# Klon.net
KiCad netlist of a schematic drawn in EAGLE
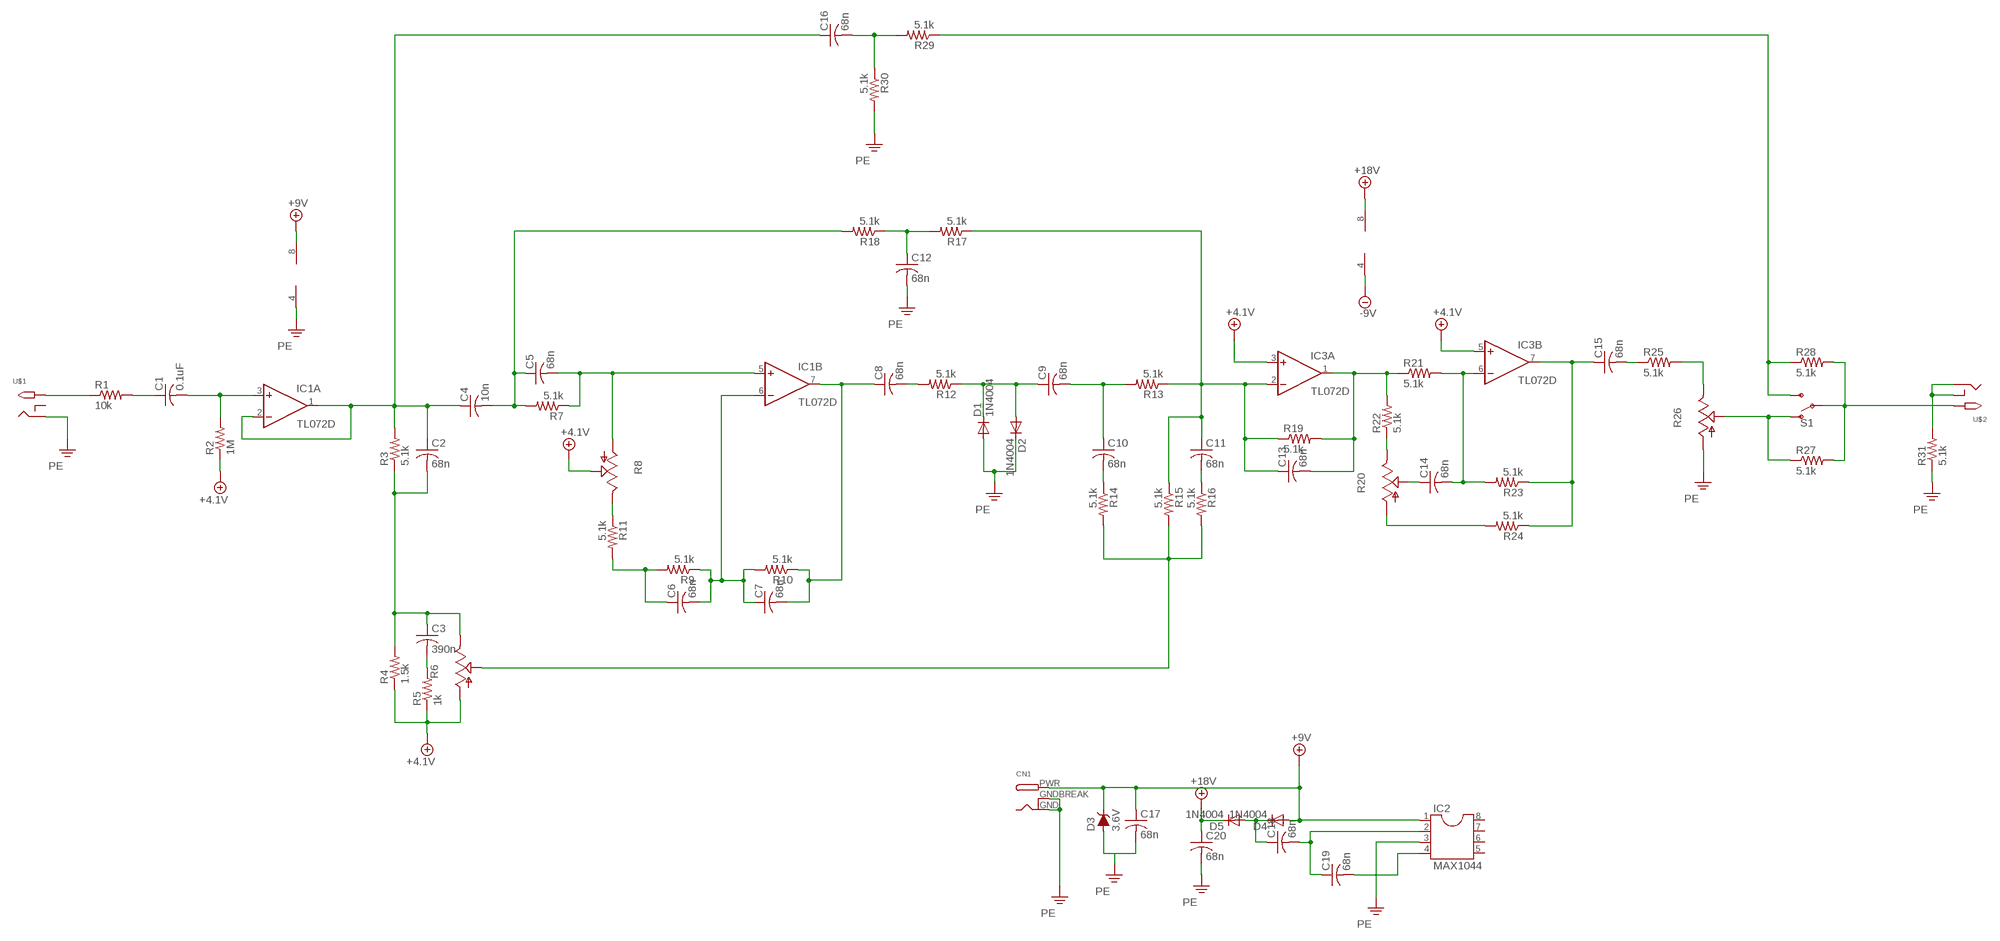
[diagram p0: schematic, sheet 1]

(export (version "E")
  (design (tool "Eeschema 10.0.6"))
  (components
    (comp (ref "C1")
      (value "0.1uF")
      (footprint "eagle-import:C0603")
      (libsource (lib "eagle-import") (part "C-USC0603"))
    )
    (comp (ref "C2")
      (value "68n")
      (footprint "eagle-import:C0603")
      (libsource (lib "eagle-import") (part "C-USC0603"))
    )
    (comp (ref "C3")
      (value "390n")
      (footprint "eagle-import:C0603")
      (libsource (lib "eagle-import") (part "C-USC0603"))
    )
    (comp (ref "C4")
      (value "10n")
      (footprint "eagle-import:C0603")
      (libsource (lib "eagle-import") (part "C-USC0603"))
    )
    (comp (ref "C5")
      (value "68n")
      (footprint "eagle-import:C0603")
      (libsource (lib "eagle-import") (part "C-USC0603"))
    )
    (comp (ref "C6")
      (value "68n")
      (footprint "eagle-import:C0603")
      (libsource (lib "eagle-import") (part "C-USC0603"))
    )
    (comp (ref "C7")
      (value "68n")
      (footprint "eagle-import:C0603")
      (libsource (lib "eagle-import") (part "C-USC0603"))
    )
    (comp (ref "C8")
      (value "68n")
      (footprint "eagle-import:C0603")
      (libsource (lib "eagle-import") (part "C-USC0603"))
    )
    (comp (ref "C9")
      (value "68n")
      (footprint "eagle-import:C0603")
      (libsource (lib "eagle-import") (part "C-USC0603"))
    )
    (comp (ref "C10")
      (value "68n")
      (footprint "eagle-import:C0603")
      (libsource (lib "eagle-import") (part "C-USC0603"))
    )
    (comp (ref "C11")
      (value "68n")
      (footprint "eagle-import:C0603")
      (libsource (lib "eagle-import") (part "C-USC0603"))
    )
    (comp (ref "C12")
      (value "68n")
      (footprint "eagle-import:C0603")
      (libsource (lib "eagle-import") (part "C-USC0603"))
    )
    (comp (ref "C13")
      (value "68n")
      (footprint "eagle-import:C0603")
      (libsource (lib "eagle-import") (part "C-USC0603"))
    )
    (comp (ref "C14")
      (value "68n")
      (footprint "eagle-import:C0603")
      (libsource (lib "eagle-import") (part "C-USC0603"))
    )
    (comp (ref "C15")
      (value "68n")
      (footprint "eagle-import:C0603")
      (libsource (lib "eagle-import") (part "C-USC0603"))
    )
    (comp (ref "C16")
      (value "68n")
      (footprint "eagle-import:C0603")
      (libsource (lib "eagle-import") (part "C-USC0603"))
    )
    (comp (ref "C17")
      (value "68n")
      (footprint "eagle-import:C0603")
      (libsource (lib "eagle-import") (part "C-USC0603"))
    )
    (comp (ref "C18")
      (value "68n")
      (footprint "eagle-import:C0603")
      (libsource (lib "eagle-import") (part "C-USC0603"))
    )
    (comp (ref "C19")
      (value "68n")
      (footprint "eagle-import:C0603")
      (libsource (lib "eagle-import") (part "C-USC0603"))
    )
    (comp (ref "C20")
      (value "68n")
      (footprint "eagle-import:C0603")
      (libsource (lib "eagle-import") (part "C-USC0603"))
    )
    (comp (ref "CN1")
      (value "DCBARRELPTH")
      (footprint "eagle-import:DCJACK_2MM_PTH")
      (libsource (lib "eagle-import") (part "DCBARRELPTH"))
    )
    (comp (ref "D1")
      (value "1N4004")
      (footprint "eagle-import:DO41-10")
      (libsource (lib "eagle-import") (part "1N4004"))
    )
    (comp (ref "D2")
      (value "1N4004")
      (footprint "eagle-import:DO41-10")
      (libsource (lib "eagle-import") (part "1N4004"))
    )
    (comp (ref "D3")
      (value "3.6V")
      (footprint "eagle-import:SOD-323")
      (libsource (lib "eagle-import") (part "DIODE-ZENER-BZT52C3V6S"))
    )
    (comp (ref "D4")
      (value "1N4004")
      (footprint "eagle-import:DO41-10")
      (libsource (lib "eagle-import") (part "1N4004"))
    )
    (comp (ref "D5")
      (value "1N4004")
      (footprint "eagle-import:DO41-10")
      (libsource (lib "eagle-import") (part "1N4004"))
    )
    (comp (ref "IC1")
      (value "TL072D")
      (footprint "eagle-import:SO08")
      (libsource (lib "eagle-import") (part "TL072D"))
    )
    (comp (ref "IC2")
      (value "MAX1044")
      (footprint "eagle-import:DIL08")
      (fields (field (name "MF") "Maxim Integrated"))
      (libsource (lib "eagle-import") (part "MAX1044"))
    )
    (comp (ref "IC3")
      (value "TL072D")
      (footprint "eagle-import:SO08")
      (libsource (lib "eagle-import") (part "TL072D"))
    )
    (comp (ref "R1")
      (value "10k")
      (footprint "eagle-import:R0603")
      (libsource (lib "eagle-import") (part "R-US_R0603"))
    )
    (comp (ref "R2")
      (value "1M")
      (footprint "eagle-import:R0603")
      (libsource (lib "eagle-import") (part "R-US_R0603"))
    )
    (comp (ref "R3")
      (value "5.1k")
      (footprint "eagle-import:R0603")
      (libsource (lib "eagle-import") (part "R-US_R0603"))
    )
    (comp (ref "R4")
      (value "1.5k")
      (footprint "eagle-import:R0603")
      (libsource (lib "eagle-import") (part "R-US_R0603"))
    )
    (comp (ref "R5")
      (value "1k")
      (footprint "eagle-import:R0603")
      (libsource (lib "eagle-import") (part "R-US_R0603"))
    )
    (comp (ref "R6")
      (value "TRIM_US-3223G")
      (footprint "eagle-import:3223G")
      (libsource (lib "eagle-import") (part "TRIM_US-3223G"))
    )
    (comp (ref "R7")
      (value "5.1k")
      (footprint "eagle-import:R0603")
      (libsource (lib "eagle-import") (part "R-US_R0603"))
    )
    (comp (ref "R8")
      (value "TRIM_US-3223G")
      (footprint "eagle-import:3223G")
      (libsource (lib "eagle-import") (part "TRIM_US-3223G"))
    )
    (comp (ref "R9")
      (value "5.1k")
      (footprint "eagle-import:R0603")
      (libsource (lib "eagle-import") (part "R-US_R0603"))
    )
    (comp (ref "R10")
      (value "5.1k")
      (footprint "eagle-import:R0603")
      (libsource (lib "eagle-import") (part "R-US_R0603"))
    )
    (comp (ref "R11")
      (value "5.1k")
      (footprint "eagle-import:R0603")
      (libsource (lib "eagle-import") (part "R-US_R0603"))
    )
    (comp (ref "R12")
      (value "5.1k")
      (footprint "eagle-import:R0603")
      (libsource (lib "eagle-import") (part "R-US_R0603"))
    )
    (comp (ref "R13")
      (value "5.1k")
      (footprint "eagle-import:R0603")
      (libsource (lib "eagle-import") (part "R-US_R0603"))
    )
    (comp (ref "R14")
      (value "5.1k")
      (footprint "eagle-import:R0603")
      (libsource (lib "eagle-import") (part "R-US_R0603"))
    )
    (comp (ref "R15")
      (value "5.1k")
      (footprint "eagle-import:R0603")
      (libsource (lib "eagle-import") (part "R-US_R0603"))
    )
    (comp (ref "R16")
      (value "5.1k")
      (footprint "eagle-import:R0603")
      (libsource (lib "eagle-import") (part "R-US_R0603"))
    )
    (comp (ref "R17")
      (value "5.1k")
      (footprint "eagle-import:R0603")
      (libsource (lib "eagle-import") (part "R-US_R0603"))
    )
    (comp (ref "R18")
      (value "5.1k")
      (footprint "eagle-import:R0603")
      (libsource (lib "eagle-import") (part "R-US_R0603"))
    )
    (comp (ref "R19")
      (value "5.1k")
      (footprint "eagle-import:R0603")
      (libsource (lib "eagle-import") (part "R-US_R0603"))
    )
    (comp (ref "R20")
      (value "TRIM_US-3223G")
      (footprint "eagle-import:3223G")
      (libsource (lib "eagle-import") (part "TRIM_US-3223G"))
    )
    (comp (ref "R21")
      (value "5.1k")
      (footprint "eagle-import:R0603")
      (libsource (lib "eagle-import") (part "R-US_R0603"))
    )
    (comp (ref "R22")
      (value "5.1k")
      (footprint "eagle-import:R0603")
      (libsource (lib "eagle-import") (part "R-US_R0603"))
    )
    (comp (ref "R23")
      (value "5.1k")
      (footprint "eagle-import:R0603")
      (libsource (lib "eagle-import") (part "R-US_R0603"))
    )
    (comp (ref "R24")
      (value "5.1k")
      (footprint "eagle-import:R0603")
      (libsource (lib "eagle-import") (part "R-US_R0603"))
    )
    (comp (ref "R25")
      (value "5.1k")
      (footprint "eagle-import:R0603")
      (libsource (lib "eagle-import") (part "R-US_R0603"))
    )
    (comp (ref "R26")
      (value "TRIM_US-3223G")
      (footprint "eagle-import:3223G")
      (libsource (lib "eagle-import") (part "TRIM_US-3223G"))
    )
    (comp (ref "R27")
      (value "5.1k")
      (footprint "eagle-import:R0603")
      (libsource (lib "eagle-import") (part "R-US_R0603"))
    )
    (comp (ref "R28")
      (value "5.1k")
      (footprint "eagle-import:R0603")
      (libsource (lib "eagle-import") (part "R-US_R0603"))
    )
    (comp (ref "R29")
      (value "5.1k")
      (footprint "eagle-import:R0603")
      (libsource (lib "eagle-import") (part "R-US_R0603"))
    )
    (comp (ref "R30")
      (value "5.1k")
      (footprint "eagle-import:R0603")
      (libsource (lib "eagle-import") (part "R-US_R0603"))
    )
    (comp (ref "R31")
      (value "5.1k")
      (footprint "eagle-import:R0603")
      (libsource (lib "eagle-import") (part "R-US_R0603"))
    )
    (comp (ref "S1")
      (value "SWITCH-SPDT-PTH-11.6X4.0MM")
      (footprint "eagle-import:SWITCH_SPDT_PTH_11.6X4.0MM")
      (libsource (lib "eagle-import") (part "SWITCH-SPDT-PTH-11.6X4.0MM"))
    )
    (comp (ref "U$1")
      (value "2.1MMJACKSMT")
      (footprint "eagle-import:DCJACK_2MM_SMT")
      (libsource (lib "eagle-import") (part "2.1MMJACKSMT"))
    )
    (comp (ref "U$2")
      (value "2.1MMJACKSMT")
      (footprint "eagle-import:DCJACK_2MM_SMT")
      (libsource (lib "eagle-import") (part "2.1MMJACKSMT"))
    )
  )
  (nets
    (net (code "1") (name "+4.1V") (class "Default")
      (node (ref "IC3") (pin "3") (pinfunction "+IN_3") (pintype "input"))
      (node (ref "IC3") (pin "5") (pinfunction "+IN_5") (pintype "input"))
      (node (ref "R2") (pin "1") (pinfunction "1_1") (pintype "passive"))
      (node (ref "R4") (pin "1") (pinfunction "1_1") (pintype "passive"))
      (node (ref "R5") (pin "1") (pinfunction "1_1") (pintype "passive"))
      (node (ref "R6") (pin "1") (pinfunction "A_1") (pintype "passive"))
      (node (ref "R8") (pin "2") (pinfunction "S_2") (pintype "passive"))
    )
    (net (code "2") (name "+9V") (class "Default")
      (node (ref "C17") (pin "1") (pinfunction "1_1") (pintype "passive"))
      (node (ref "CN1") (pin "PWR") (pinfunction "PWR_PWR") (pintype "power_in"))
      (node (ref "D3") (pin "C") (pinfunction "C_C") (pintype "passive"))
      (node (ref "D4") (pin "A") (pinfunction "A_A") (pintype "passive"))
      (node (ref "IC1") (pin "8") (pinfunction "V+_8") (pintype "power_in"))
      (node (ref "IC2") (pin "1") (pinfunction "1_1") (pintype "passive"))
    )
    (net (code "3") (name "+18V") (class "Default")
      (node (ref "C20") (pin "1") (pinfunction "1_1") (pintype "passive"))
      (node (ref "D5") (pin "C") (pinfunction "C_C") (pintype "passive"))
      (node (ref "IC3") (pin "8") (pinfunction "V+_8") (pintype "power_in"))
    )
    (net (code "4") (name "-9V") (class "Default")
      (node (ref "IC3") (pin "4") (pinfunction "V-_4") (pintype "power_in"))
    )
    (net (code "5") (name "Net-(C1-Pad1)") (class "Default")
      (node (ref "C1") (pin "1") (pinfunction "1_1") (pintype "passive"))
      (node (ref "R1") (pin "2") (pinfunction "2_2") (pintype "passive"))
    )
    (net (code "6") (name "Net-(C3-Pad2)") (class "Default")
      (node (ref "C3") (pin "2") (pinfunction "2_2") (pintype "passive"))
      (node (ref "R5") (pin "2") (pinfunction "2_2") (pintype "passive"))
    )
    (net (code "7") (name "Net-(C4-Pad2)") (class "Default")
      (node (ref "C4") (pin "2") (pinfunction "2_2") (pintype "passive"))
      (node (ref "C5") (pin "1") (pinfunction "1_1") (pintype "passive"))
      (node (ref "R18") (pin "2") (pinfunction "2_2") (pintype "passive"))
      (node (ref "R7") (pin "2") (pinfunction "2_2") (pintype "passive"))
    )
    (net (code "8") (name "Net-(C6-Pad1)") (class "Default")
      (node (ref "C6") (pin "1") (pinfunction "1_1") (pintype "passive"))
      (node (ref "R11") (pin "2") (pinfunction "2_2") (pintype "passive"))
      (node (ref "R9") (pin "2") (pinfunction "2_2") (pintype "passive"))
    )
    (net (code "9") (name "Net-(C8-Pad2)") (class "Default")
      (node (ref "C8") (pin "2") (pinfunction "2_2") (pintype "passive"))
      (node (ref "R12") (pin "2") (pinfunction "2_2") (pintype "passive"))
    )
    (net (code "10") (name "Net-(C9-Pad1)") (class "Default")
      (node (ref "C9") (pin "1") (pinfunction "1_1") (pintype "passive"))
      (node (ref "D1") (pin "C") (pinfunction "C_C") (pintype "passive"))
      (node (ref "D2") (pin "A") (pinfunction "A_A") (pintype "passive"))
      (node (ref "R12") (pin "1") (pinfunction "1_1") (pintype "passive"))
    )
    (net (code "11") (name "Net-(C10-Pad1)") (class "Default")
      (node (ref "C10") (pin "1") (pinfunction "1_1") (pintype "passive"))
      (node (ref "C9") (pin "2") (pinfunction "2_2") (pintype "passive"))
      (node (ref "R13") (pin "2") (pinfunction "2_2") (pintype "passive"))
    )
    (net (code "12") (name "Net-(C10-Pad2)") (class "Default")
      (node (ref "C10") (pin "2") (pinfunction "2_2") (pintype "passive"))
      (node (ref "R14") (pin "1") (pinfunction "1_1") (pintype "passive"))
    )
    (net (code "13") (name "Net-(C11-Pad2)") (class "Default")
      (node (ref "C11") (pin "2") (pinfunction "2_2") (pintype "passive"))
      (node (ref "R16") (pin "1") (pinfunction "1_1") (pintype "passive"))
    )
    (net (code "14") (name "Net-(C12-Pad1)") (class "Default")
      (node (ref "C12") (pin "1") (pinfunction "1_1") (pintype "passive"))
      (node (ref "R17") (pin "2") (pinfunction "2_2") (pintype "passive"))
      (node (ref "R18") (pin "1") (pinfunction "1_1") (pintype "passive"))
    )
    (net (code "15") (name "Net-(C15-Pad2)") (class "Default")
      (node (ref "C15") (pin "2") (pinfunction "2_2") (pintype "passive"))
      (node (ref "R25") (pin "1") (pinfunction "1_1") (pintype "passive"))
    )
    (net (code "16") (name "Net-(C16-Pad2)") (class "Default")
      (node (ref "C16") (pin "2") (pinfunction "2_2") (pintype "passive"))
      (node (ref "R29") (pin "2") (pinfunction "2_2") (pintype "passive"))
      (node (ref "R30") (pin "1") (pinfunction "1_1") (pintype "passive"))
    )
    (net (code "17") (name "Net-(C18-Pad1)") (class "Default")
      (node (ref "C18") (pin "1") (pinfunction "1_1") (pintype "passive"))
      (node (ref "D4") (pin "C") (pinfunction "C_C") (pintype "passive"))
      (node (ref "D5") (pin "A") (pinfunction "A_A") (pintype "passive"))
    )
    (net (code "18") (name "Net-(C18-Pad2)") (class "Default")
      (node (ref "C18") (pin "2") (pinfunction "2_2") (pintype "passive"))
      (node (ref "C19") (pin "1") (pinfunction "1_1") (pintype "passive"))
      (node (ref "IC2") (pin "2") (pinfunction "2_2") (pintype "passive"))
    )
    (net (code "19") (name "Net-(C19-Pad2)") (class "Default")
      (node (ref "C19") (pin "2") (pinfunction "2_2") (pintype "passive"))
      (node (ref "IC2") (pin "4") (pinfunction "4_4") (pintype "passive"))
    )
    (net (code "20") (name "Net-(IC1A-+IN)") (class "Default")
      (node (ref "C1") (pin "2") (pinfunction "2_2") (pintype "passive"))
      (node (ref "IC1") (pin "3") (pinfunction "+IN_3") (pintype "input"))
      (node (ref "R2") (pin "2") (pinfunction "2_2") (pintype "passive"))
    )
    (net (code "21") (name "Net-(IC1A--IN)") (class "Default")
      (node (ref "C16") (pin "1") (pinfunction "1_1") (pintype "passive"))
      (node (ref "C2") (pin "1") (pinfunction "1_1") (pintype "passive"))
      (node (ref "C4") (pin "1") (pinfunction "1_1") (pintype "passive"))
      (node (ref "IC1") (pin "1") (pinfunction "OUT_1") (pintype "output"))
      (node (ref "IC1") (pin "2") (pinfunction "-IN_2") (pintype "input"))
      (node (ref "R3") (pin "2") (pinfunction "2_2") (pintype "passive"))
    )
    (net (code "22") (name "Net-(IC1B-+IN)") (class "Default")
      (node (ref "C5") (pin "2") (pinfunction "2_2") (pintype "passive"))
      (node (ref "IC1") (pin "5") (pinfunction "+IN_5") (pintype "input"))
      (node (ref "R7") (pin "1") (pinfunction "1_1") (pintype "passive"))
      (node (ref "R8") (pin "1") (pinfunction "A_1") (pintype "passive"))
    )
    (net (code "23") (name "Net-(IC1B--IN)") (class "Default")
      (node (ref "C6") (pin "2") (pinfunction "2_2") (pintype "passive"))
      (node (ref "C7") (pin "1") (pinfunction "1_1") (pintype "passive"))
      (node (ref "IC1") (pin "6") (pinfunction "-IN_6") (pintype "input"))
      (node (ref "R10") (pin "2") (pinfunction "2_2") (pintype "passive"))
      (node (ref "R9") (pin "1") (pinfunction "1_1") (pintype "passive"))
    )
    (net (code "24") (name "Net-(IC1B-OUT)") (class "Default")
      (node (ref "C7") (pin "2") (pinfunction "2_2") (pintype "passive"))
      (node (ref "C8") (pin "1") (pinfunction "1_1") (pintype "passive"))
      (node (ref "IC1") (pin "7") (pinfunction "OUT_7") (pintype "output"))
      (node (ref "R10") (pin "1") (pinfunction "1_1") (pintype "passive"))
    )
    (net (code "25") (name "Net-(IC3A--IN)") (class "Default")
      (node (ref "C11") (pin "1") (pinfunction "1_1") (pintype "passive"))
      (node (ref "C13") (pin "1") (pinfunction "1_1") (pintype "passive"))
      (node (ref "IC3") (pin "2") (pinfunction "-IN_2") (pintype "input"))
      (node (ref "R13") (pin "1") (pinfunction "1_1") (pintype "passive"))
      (node (ref "R15") (pin "1") (pinfunction "1_1") (pintype "passive"))
      (node (ref "R17") (pin "1") (pinfunction "1_1") (pintype "passive"))
      (node (ref "R19") (pin "1") (pinfunction "1_1") (pintype "passive"))
    )
    (net (code "26") (name "Net-(IC3A-OUT)") (class "Default")
      (node (ref "C13") (pin "2") (pinfunction "2_2") (pintype "passive"))
      (node (ref "IC3") (pin "1") (pinfunction "OUT_1") (pintype "output"))
      (node (ref "R19") (pin "2") (pinfunction "2_2") (pintype "passive"))
      (node (ref "R21") (pin "1") (pinfunction "1_1") (pintype "passive"))
      (node (ref "R22") (pin "2") (pinfunction "2_2") (pintype "passive"))
    )
    (net (code "27") (name "Net-(IC3B--IN)") (class "Default")
      (node (ref "C14") (pin "2") (pinfunction "2_2") (pintype "passive"))
      (node (ref "IC3") (pin "6") (pinfunction "-IN_6") (pintype "input"))
      (node (ref "R21") (pin "2") (pinfunction "2_2") (pintype "passive"))
      (node (ref "R23") (pin "2") (pinfunction "2_2") (pintype "passive"))
    )
    (net (code "28") (name "Net-(IC3B-OUT)") (class "Default")
      (node (ref "C15") (pin "1") (pinfunction "1_1") (pintype "passive"))
      (node (ref "IC3") (pin "7") (pinfunction "OUT_7") (pintype "output"))
      (node (ref "R23") (pin "1") (pinfunction "1_1") (pintype "passive"))
      (node (ref "R24") (pin "1") (pinfunction "1_1") (pintype "passive"))
    )
    (net (code "29") (name "Net-(R6-E)") (class "Default")
      (node (ref "C2") (pin "2") (pinfunction "2_2") (pintype "passive"))
      (node (ref "C3") (pin "1") (pinfunction "1_1") (pintype "passive"))
      (node (ref "R3") (pin "1") (pinfunction "1_1") (pintype "passive"))
      (node (ref "R4") (pin "2") (pinfunction "2_2") (pintype "passive"))
      (node (ref "R6") (pin "3") (pinfunction "E_3") (pintype "passive"))
    )
    (net (code "30") (name "Net-(R6-S)") (class "Default")
      (node (ref "R14") (pin "2") (pinfunction "2_2") (pintype "passive"))
      (node (ref "R15") (pin "2") (pinfunction "2_2") (pintype "passive"))
      (node (ref "R16") (pin "2") (pinfunction "2_2") (pintype "passive"))
      (node (ref "R6") (pin "2") (pinfunction "S_2") (pintype "passive"))
    )
    (net (code "31") (name "Net-(R8-E)") (class "Default")
      (node (ref "R11") (pin "1") (pinfunction "1_1") (pintype "passive"))
      (node (ref "R8") (pin "3") (pinfunction "E_3") (pintype "passive"))
    )
    (net (code "32") (name "Net-(R20-A)") (class "Default")
      (node (ref "R20") (pin "1") (pinfunction "A_1") (pintype "passive"))
      (node (ref "R24") (pin "2") (pinfunction "2_2") (pintype "passive"))
    )
    (net (code "33") (name "Net-(R20-E)") (class "Default")
      (node (ref "R20") (pin "3") (pinfunction "E_3") (pintype "passive"))
      (node (ref "R22") (pin "1") (pinfunction "1_1") (pintype "passive"))
    )
    (net (code "34") (name "Net-(R20-S)") (class "Default")
      (node (ref "C14") (pin "1") (pinfunction "1_1") (pintype "passive"))
      (node (ref "R20") (pin "2") (pinfunction "S_2") (pintype "passive"))
    )
    (net (code "35") (name "Net-(R26-E)") (class "Default")
      (node (ref "R25") (pin "2") (pinfunction "2_2") (pintype "passive"))
      (node (ref "R26") (pin "3") (pinfunction "E_3") (pintype "passive"))
    )
    (net (code "36") (name "Net-(R26-S)") (class "Default")
      (node (ref "R26") (pin "2") (pinfunction "S_2") (pintype "passive"))
      (node (ref "R27") (pin "1") (pinfunction "1_1") (pintype "passive"))
      (node (ref "S1") (pin "1") (pinfunction "O_1") (pintype "passive"))
    )
    (net (code "37") (name "Net-(S1-P)") (class "Default")
      (node (ref "R27") (pin "2") (pinfunction "2_2") (pintype "passive"))
      (node (ref "R28") (pin "2") (pinfunction "2_2") (pintype "passive"))
      (node (ref "S1") (pin "2") (pinfunction "P_2") (pintype "passive"))
      (node (ref "U$2") (pin "PWR2") (pinfunction "TIP_PWR2") (pintype "bidirectional"))
    )
    (net (code "38") (name "Net-(S1-S)") (class "Default")
      (node (ref "R28") (pin "1") (pinfunction "1_1") (pintype "passive"))
      (node (ref "R29") (pin "1") (pinfunction "1_1") (pintype "passive"))
      (node (ref "S1") (pin "3") (pinfunction "S_3") (pintype "passive"))
    )
    (net (code "39") (name "Net-(U$1-TIP)") (class "Default")
      (node (ref "R1") (pin "1") (pinfunction "1_1") (pintype "passive"))
      (node (ref "U$1") (pin "PWR2") (pinfunction "TIP_PWR2") (pintype "bidirectional"))
    )
    (net (code "40") (name "Net-(U$2-RING)") (class "Default")
      (node (ref "R31") (pin "2") (pinfunction "2_2") (pintype "passive"))
      (node (ref "U$2") (pin "GND") (pinfunction "RING_GND") (pintype "bidirectional"))
      (node (ref "U$2") (pin "GNDBREAK") (pinfunction "RING_SW_GNDBREAK") (pintype "bidirectional"))
    )
    (net (code "41") (name "PE") (class "Default")
      (node (ref "C12") (pin "2") (pinfunction "2_2") (pintype "passive"))
      (node (ref "C17") (pin "2") (pinfunction "2_2") (pintype "passive"))
      (node (ref "C20") (pin "2") (pinfunction "2_2") (pintype "passive"))
      (node (ref "CN1") (pin "GND") (pinfunction "GND_GND") (pintype "power_in"))
      (node (ref "CN1") (pin "GNDBREAK") (pinfunction "GNDBREAK_GNDBREAK") (pintype "power_in"))
      (node (ref "D1") (pin "A") (pinfunction "A_A") (pintype "passive"))
      (node (ref "D2") (pin "C") (pinfunction "C_C") (pintype "passive"))
      (node (ref "D3") (pin "A") (pinfunction "A_A") (pintype "passive"))
      (node (ref "IC1") (pin "4") (pinfunction "V-_4") (pintype "power_in"))
      (node (ref "IC2") (pin "3") (pinfunction "3_3") (pintype "passive"))
      (node (ref "R26") (pin "1") (pinfunction "A_1") (pintype "passive"))
      (node (ref "R30") (pin "2") (pinfunction "2_2") (pintype "passive"))
      (node (ref "R31") (pin "1") (pinfunction "1_1") (pintype "passive"))
      (node (ref "U$1") (pin "GND") (pinfunction "RING_GND") (pintype "bidirectional"))
    )
    (net (code "42") (name "unconnected-(IC2-Pad5)") (class "Default")
      (node (ref "IC2") (pin "5") (pinfunction "5_5") (pintype "passive"))
    )
    (net (code "43") (name "unconnected-(IC2-Pad6)") (class "Default")
      (node (ref "IC2") (pin "6") (pinfunction "6_6") (pintype "passive"))
    )
    (net (code "44") (name "unconnected-(IC2-Pad7)") (class "Default")
      (node (ref "IC2") (pin "7") (pinfunction "7_7") (pintype "passive"))
    )
    (net (code "45") (name "unconnected-(IC2-Pad8)") (class "Default")
      (node (ref "IC2") (pin "8") (pinfunction "8_8") (pintype "passive"))
    )
    (net (code "46") (name "unconnected-(U$1-RING_SW-PadGNDBREAK)") (class "Default")
      (node (ref "U$1") (pin "GNDBREAK") (pinfunction "RING_SW_GNDBREAK") (pintype "bidirectional"))
    )
  )
)
